# v3.net
KiCad netlist of a schematic drawn in Altium Designer
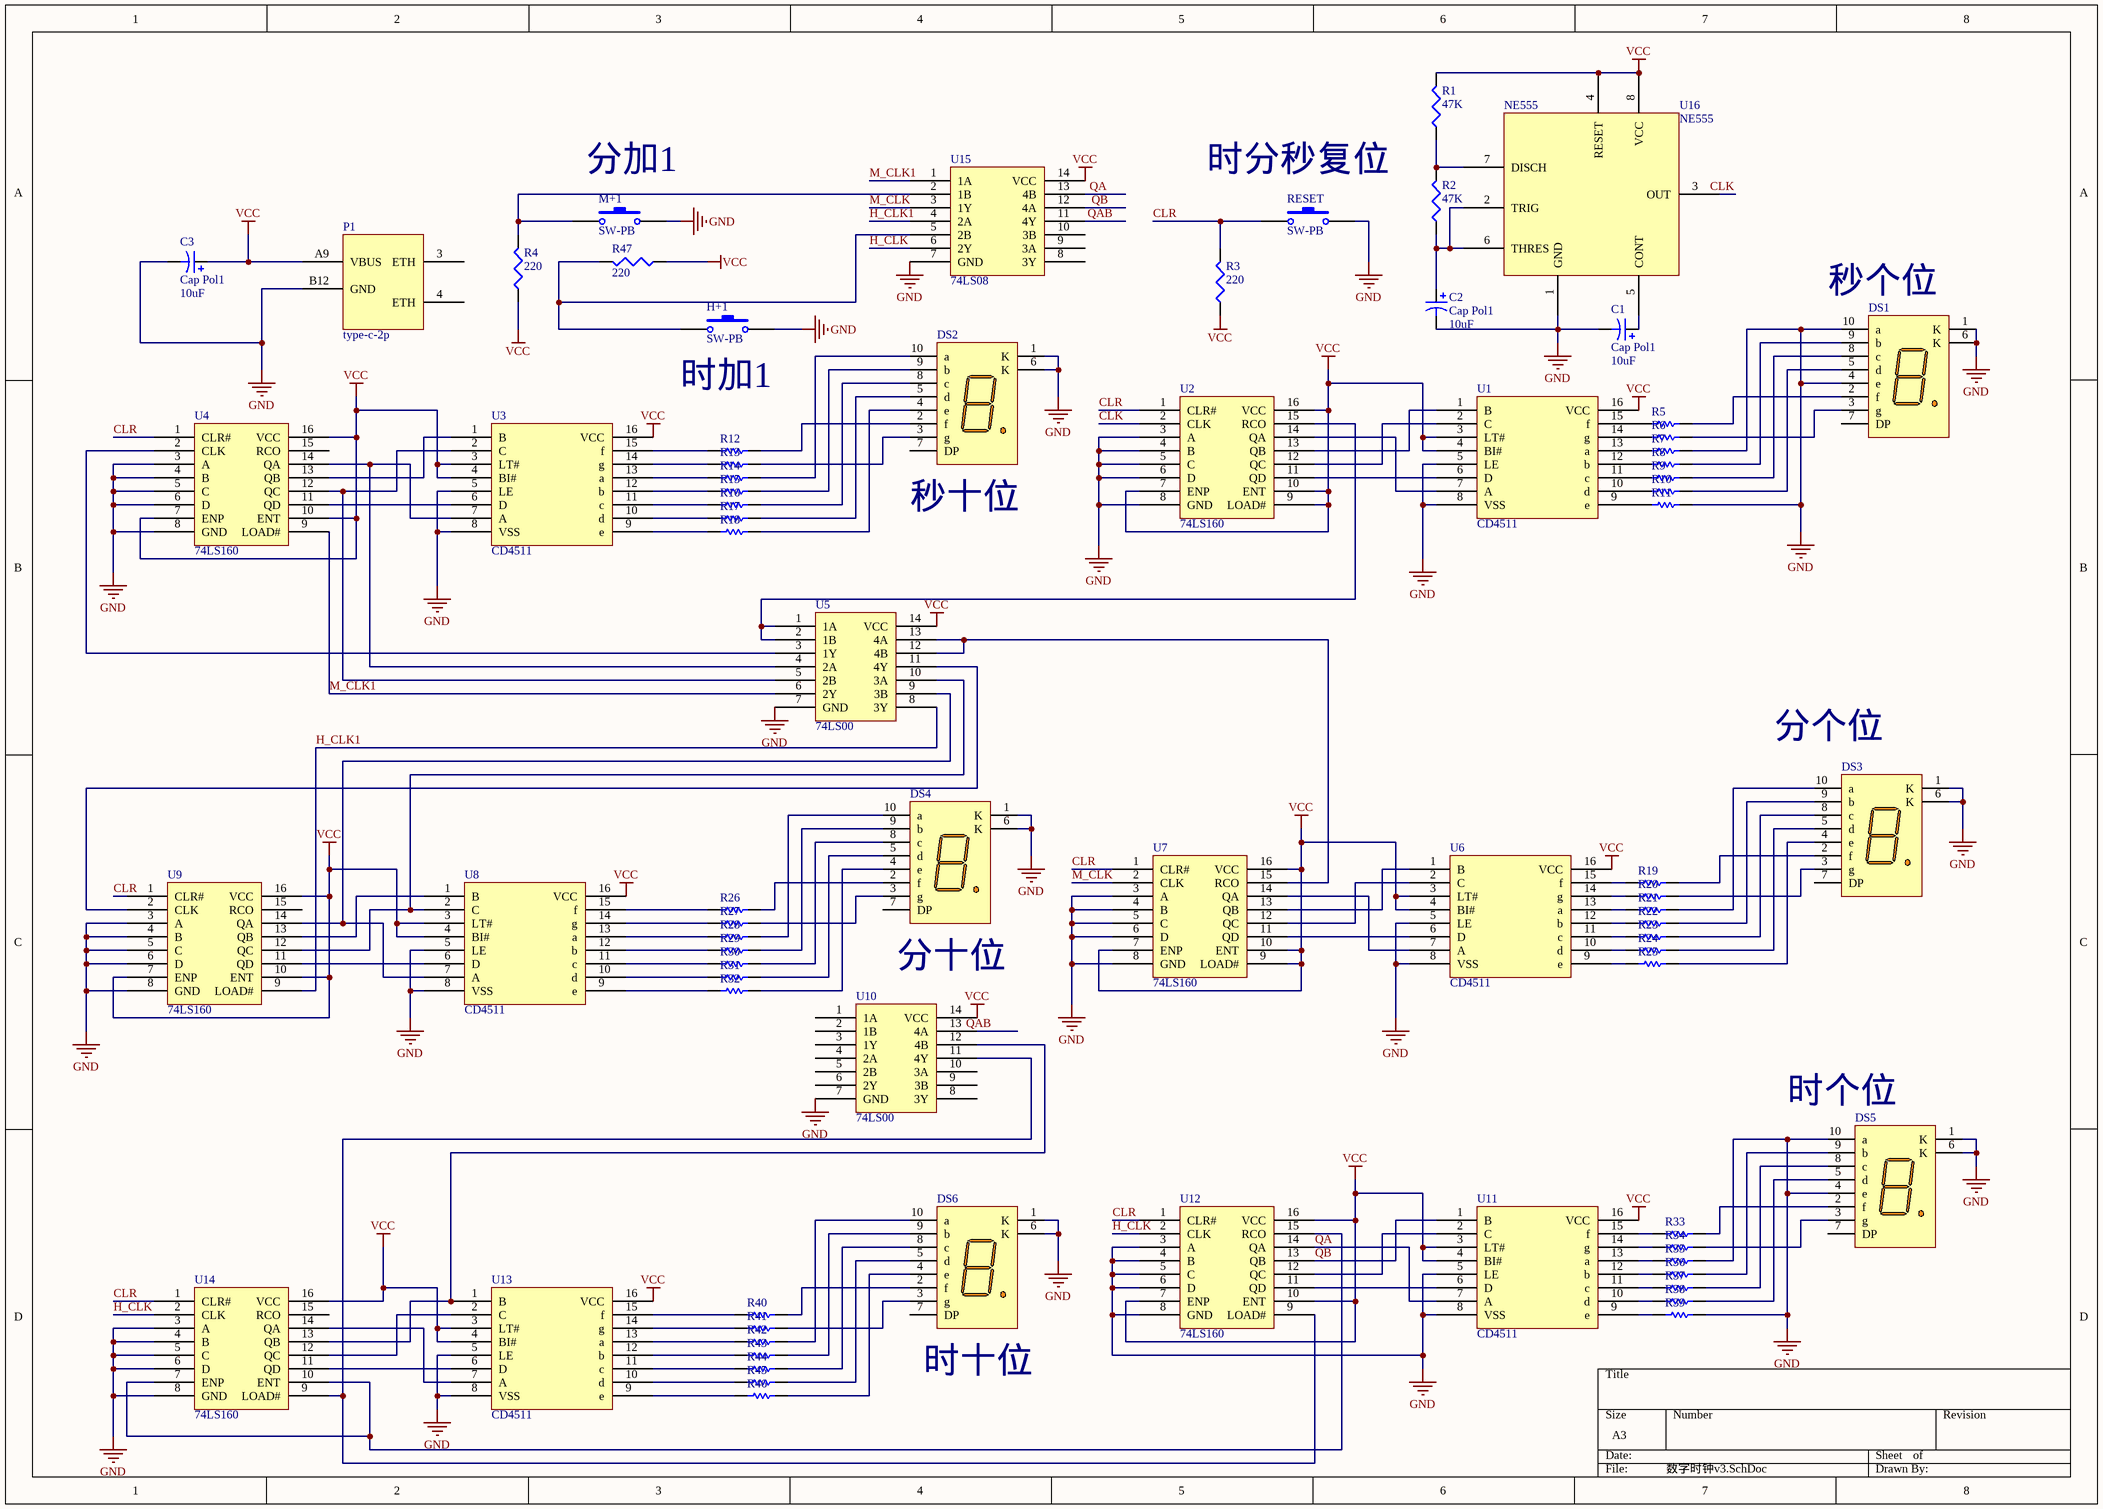
[diagram p0: 数字时钟v3.SchDoc]

(export (version "E")
  (design (tool "Eeschema 10.0.6"))
  (components
    (comp (ref "C1")
      (value "Cap Pol1")
      (footprint "电容")
      (description "Polarized Capacitor (Radial)")
      (fields (field (name "ALTIUM_VALUE") "10uF") (field (name "PUBLISHER") "Altium Limited"))
      (libsource (lib "Miscellaneous Devices") (part "Cap Pol1"))
    )
    (comp (ref "C2")
      (value "Cap Pol1")
      (footprint "电容")
      (description "Polarized Capacitor (Radial)")
      (fields (field (name "ALTIUM_VALUE") "10uF") (field (name "PUBLISHER") "Altium Limited"))
      (libsource (lib "Miscellaneous Devices") (part "Cap Pol1"))
    )
    (comp (ref "C3")
      (value "Cap Pol1")
      (footprint "电容")
      (description "Polarized Capacitor (Radial)")
      (fields (field (name "ALTIUM_VALUE") "10uF") (field (name "PUBLISHER") "Altium Limited"))
      (libsource (lib "Miscellaneous Devices") (part "Cap Pol1"))
    )
    (comp (ref "DS1")
      (value "Dpy Amber-CC")
      (footprint "A")
      (description "7.62 mm Black Surface Orange 7-Segment Display: CC, RH DP")
      (fields (field (name "PUBLISHER") "Altium Limited"))
      (libsource (lib "Miscellaneous Devices") (part "Dpy Amber-CC"))
    )
    (comp (ref "DS2")
      (value "Dpy Amber-CC")
      (footprint "A")
      (description "7.62 mm Black Surface Orange 7-Segment Display: CC, RH DP")
      (fields (field (name "PUBLISHER") "Altium Limited"))
      (libsource (lib "Miscellaneous Devices") (part "Dpy Amber-CC"))
    )
    (comp (ref "DS3")
      (value "Dpy Amber-CC")
      (footprint "A")
      (description "7.62 mm Black Surface Orange 7-Segment Display: CC, RH DP")
      (fields (field (name "PUBLISHER") "Altium Limited"))
      (libsource (lib "Miscellaneous Devices") (part "Dpy Amber-CC"))
    )
    (comp (ref "DS4")
      (value "Dpy Amber-CC")
      (footprint "A")
      (description "7.62 mm Black Surface Orange 7-Segment Display: CC, RH DP")
      (fields (field (name "PUBLISHER") "Altium Limited"))
      (libsource (lib "Miscellaneous Devices") (part "Dpy Amber-CC"))
    )
    (comp (ref "DS5")
      (value "Dpy Amber-CC")
      (footprint "A")
      (description "7.62 mm Black Surface Orange 7-Segment Display: CC, RH DP")
      (fields (field (name "PUBLISHER") "Altium Limited"))
      (libsource (lib "Miscellaneous Devices") (part "Dpy Amber-CC"))
    )
    (comp (ref "DS6")
      (value "Dpy Amber-CC")
      (footprint "A")
      (description "7.62 mm Black Surface Orange 7-Segment Display: CC, RH DP")
      (fields (field (name "PUBLISHER") "Altium Limited"))
      (libsource (lib "Miscellaneous Devices") (part "Dpy Amber-CC"))
    )
    (comp (ref "H+1")
      (value "SW-PB")
      (footprint "按键")
      (description "Switch")
      (fields (field (name "PUBLISHER") "Altium Limited"))
      (libsource (lib "Miscellaneous Devices") (part "SW-PB"))
    )
    (comp (ref "M+1")
      (value "SW-PB")
      (footprint "按键")
      (description "Switch")
      (fields (field (name "PUBLISHER") "Altium Limited"))
      (libsource (lib "Miscellaneous Devices") (part "SW-PB"))
    )
    (comp (ref "P1")
      (value "type-c-2p")
      (footprint "type-c-2p")
      (libsource (lib "数字电路时钟") (part "type-c-2p"))
    )
    (comp (ref "R1")
      (value "47K")
      (footprint "AXIAL-0.3")
      (description "Resistor")
      (fields (field (name "Comment") "Res3") (field (name "PUBLISHER") "Altium Limited"))
      (libsource (lib "Miscellaneous Devices") (part "Res3"))
    )
    (comp (ref "R2")
      (value "47K")
      (footprint "AXIAL-0.3")
      (description "Resistor")
      (fields (field (name "Comment") "Res3") (field (name "PUBLISHER") "Altium Limited"))
      (libsource (lib "Miscellaneous Devices") (part "Res3"))
    )
    (comp (ref "R3")
      (value "220")
      (footprint "AXIAL-0.3")
      (description "Resistor")
      (fields (field (name "Comment") "Res3") (field (name "PUBLISHER") "Altium Limited"))
      (libsource (lib "Miscellaneous Devices") (part "Res3"))
    )
    (comp (ref "R4")
      (value "220")
      (footprint "AXIAL-0.3")
      (description "Resistor")
      (fields (field (name "Comment") "Res3") (field (name "PUBLISHER") "Altium Limited"))
      (libsource (lib "Miscellaneous Devices") (part "Res3"))
    )
    (comp (ref "R5")
      (value "Res1")
      (footprint "AXIAL-0.3")
      (description "Resistor")
      (fields (field (name "PUBLISHER") "Altium Limited"))
      (libsource (lib "Miscellaneous Devices") (part "Res1"))
    )
    (comp (ref "R6")
      (value "Res1")
      (footprint "AXIAL-0.3")
      (description "Resistor")
      (fields (field (name "PUBLISHER") "Altium Limited"))
      (libsource (lib "Miscellaneous Devices") (part "Res1"))
    )
    (comp (ref "R7")
      (value "Res1")
      (footprint "AXIAL-0.3")
      (description "Resistor")
      (fields (field (name "PUBLISHER") "Altium Limited"))
      (libsource (lib "Miscellaneous Devices") (part "Res1"))
    )
    (comp (ref "R8")
      (value "Res1")
      (footprint "AXIAL-0.3")
      (description "Resistor")
      (fields (field (name "PUBLISHER") "Altium Limited"))
      (libsource (lib "Miscellaneous Devices") (part "Res1"))
    )
    (comp (ref "R9")
      (value "Res1")
      (footprint "AXIAL-0.3")
      (description "Resistor")
      (fields (field (name "PUBLISHER") "Altium Limited"))
      (libsource (lib "Miscellaneous Devices") (part "Res1"))
    )
    (comp (ref "R10")
      (value "Res1")
      (footprint "AXIAL-0.3")
      (description "Resistor")
      (fields (field (name "PUBLISHER") "Altium Limited"))
      (libsource (lib "Miscellaneous Devices") (part "Res1"))
    )
    (comp (ref "R11")
      (value "Res1")
      (footprint "AXIAL-0.3")
      (description "Resistor")
      (fields (field (name "PUBLISHER") "Altium Limited"))
      (libsource (lib "Miscellaneous Devices") (part "Res1"))
    )
    (comp (ref "R12")
      (value "Res1")
      (footprint "AXIAL-0.3")
      (description "Resistor")
      (fields (field (name "PUBLISHER") "Altium Limited"))
      (libsource (lib "Miscellaneous Devices") (part "Res1"))
    )
    (comp (ref "R13")
      (value "Res1")
      (footprint "AXIAL-0.3")
      (description "Resistor")
      (fields (field (name "PUBLISHER") "Altium Limited"))
      (libsource (lib "Miscellaneous Devices") (part "Res1"))
    )
    (comp (ref "R14")
      (value "Res1")
      (footprint "AXIAL-0.3")
      (description "Resistor")
      (fields (field (name "PUBLISHER") "Altium Limited"))
      (libsource (lib "Miscellaneous Devices") (part "Res1"))
    )
    (comp (ref "R15")
      (value "Res1")
      (footprint "AXIAL-0.3")
      (description "Resistor")
      (fields (field (name "PUBLISHER") "Altium Limited"))
      (libsource (lib "Miscellaneous Devices") (part "Res1"))
    )
    (comp (ref "R16")
      (value "Res1")
      (footprint "AXIAL-0.3")
      (description "Resistor")
      (fields (field (name "PUBLISHER") "Altium Limited"))
      (libsource (lib "Miscellaneous Devices") (part "Res1"))
    )
    (comp (ref "R17")
      (value "Res1")
      (footprint "AXIAL-0.3")
      (description "Resistor")
      (fields (field (name "PUBLISHER") "Altium Limited"))
      (libsource (lib "Miscellaneous Devices") (part "Res1"))
    )
    (comp (ref "R18")
      (value "Res1")
      (footprint "AXIAL-0.3")
      (description "Resistor")
      (fields (field (name "PUBLISHER") "Altium Limited"))
      (libsource (lib "Miscellaneous Devices") (part "Res1"))
    )
    (comp (ref "R19")
      (value "Res1")
      (footprint "AXIAL-0.3")
      (description "Resistor")
      (fields (field (name "PUBLISHER") "Altium Limited"))
      (libsource (lib "Miscellaneous Devices") (part "Res1"))
    )
    (comp (ref "R20")
      (value "Res1")
      (footprint "AXIAL-0.3")
      (description "Resistor")
      (fields (field (name "PUBLISHER") "Altium Limited"))
      (libsource (lib "Miscellaneous Devices") (part "Res1"))
    )
    (comp (ref "R21")
      (value "Res1")
      (footprint "AXIAL-0.3")
      (description "Resistor")
      (fields (field (name "PUBLISHER") "Altium Limited"))
      (libsource (lib "Miscellaneous Devices") (part "Res1"))
    )
    (comp (ref "R22")
      (value "Res1")
      (footprint "AXIAL-0.3")
      (description "Resistor")
      (fields (field (name "PUBLISHER") "Altium Limited"))
      (libsource (lib "Miscellaneous Devices") (part "Res1"))
    )
    (comp (ref "R23")
      (value "Res1")
      (footprint "AXIAL-0.3")
      (description "Resistor")
      (fields (field (name "PUBLISHER") "Altium Limited"))
      (libsource (lib "Miscellaneous Devices") (part "Res1"))
    )
    (comp (ref "R24")
      (value "Res1")
      (footprint "AXIAL-0.3")
      (description "Resistor")
      (fields (field (name "PUBLISHER") "Altium Limited"))
      (libsource (lib "Miscellaneous Devices") (part "Res1"))
    )
    (comp (ref "R25")
      (value "Res1")
      (footprint "AXIAL-0.3")
      (description "Resistor")
      (fields (field (name "PUBLISHER") "Altium Limited"))
      (libsource (lib "Miscellaneous Devices") (part "Res1"))
    )
    (comp (ref "R26")
      (value "Res1")
      (footprint "AXIAL-0.3")
      (description "Resistor")
      (fields (field (name "PUBLISHER") "Altium Limited"))
      (libsource (lib "Miscellaneous Devices") (part "Res1"))
    )
    (comp (ref "R27")
      (value "Res1")
      (footprint "AXIAL-0.3")
      (description "Resistor")
      (fields (field (name "PUBLISHER") "Altium Limited"))
      (libsource (lib "Miscellaneous Devices") (part "Res1"))
    )
    (comp (ref "R28")
      (value "Res1")
      (footprint "AXIAL-0.3")
      (description "Resistor")
      (fields (field (name "PUBLISHER") "Altium Limited"))
      (libsource (lib "Miscellaneous Devices") (part "Res1"))
    )
    (comp (ref "R29")
      (value "Res1")
      (footprint "AXIAL-0.3")
      (description "Resistor")
      (fields (field (name "PUBLISHER") "Altium Limited"))
      (libsource (lib "Miscellaneous Devices") (part "Res1"))
    )
    (comp (ref "R30")
      (value "Res1")
      (footprint "AXIAL-0.3")
      (description "Resistor")
      (fields (field (name "PUBLISHER") "Altium Limited"))
      (libsource (lib "Miscellaneous Devices") (part "Res1"))
    )
    (comp (ref "R31")
      (value "Res1")
      (footprint "AXIAL-0.3")
      (description "Resistor")
      (fields (field (name "PUBLISHER") "Altium Limited"))
      (libsource (lib "Miscellaneous Devices") (part "Res1"))
    )
    (comp (ref "R32")
      (value "Res1")
      (footprint "AXIAL-0.3")
      (description "Resistor")
      (fields (field (name "PUBLISHER") "Altium Limited"))
      (libsource (lib "Miscellaneous Devices") (part "Res1"))
    )
    (comp (ref "R33")
      (value "Res1")
      (footprint "AXIAL-0.3")
      (description "Resistor")
      (fields (field (name "PUBLISHER") "Altium Limited"))
      (libsource (lib "Miscellaneous Devices") (part "Res1"))
    )
    (comp (ref "R34")
      (value "Res1")
      (footprint "AXIAL-0.3")
      (description "Resistor")
      (fields (field (name "PUBLISHER") "Altium Limited"))
      (libsource (lib "Miscellaneous Devices") (part "Res1"))
    )
    (comp (ref "R35")
      (value "Res1")
      (footprint "AXIAL-0.3")
      (description "Resistor")
      (fields (field (name "PUBLISHER") "Altium Limited"))
      (libsource (lib "Miscellaneous Devices") (part "Res1"))
    )
    (comp (ref "R36")
      (value "Res1")
      (footprint "AXIAL-0.3")
      (description "Resistor")
      (fields (field (name "PUBLISHER") "Altium Limited"))
      (libsource (lib "Miscellaneous Devices") (part "Res1"))
    )
    (comp (ref "R37")
      (value "Res1")
      (footprint "AXIAL-0.3")
      (description "Resistor")
      (fields (field (name "PUBLISHER") "Altium Limited"))
      (libsource (lib "Miscellaneous Devices") (part "Res1"))
    )
    (comp (ref "R38")
      (value "Res1")
      (footprint "AXIAL-0.3")
      (description "Resistor")
      (fields (field (name "PUBLISHER") "Altium Limited"))
      (libsource (lib "Miscellaneous Devices") (part "Res1"))
    )
    (comp (ref "R39")
      (value "Res1")
      (footprint "AXIAL-0.3")
      (description "Resistor")
      (fields (field (name "PUBLISHER") "Altium Limited"))
      (libsource (lib "Miscellaneous Devices") (part "Res1"))
    )
    (comp (ref "R40")
      (value "Res1")
      (footprint "AXIAL-0.3")
      (description "Resistor")
      (fields (field (name "PUBLISHER") "Altium Limited"))
      (libsource (lib "Miscellaneous Devices") (part "Res1"))
    )
    (comp (ref "R41")
      (value "Res1")
      (footprint "AXIAL-0.3")
      (description "Resistor")
      (fields (field (name "PUBLISHER") "Altium Limited"))
      (libsource (lib "Miscellaneous Devices") (part "Res1"))
    )
    (comp (ref "R42")
      (value "Res1")
      (footprint "AXIAL-0.3")
      (description "Resistor")
      (fields (field (name "PUBLISHER") "Altium Limited"))
      (libsource (lib "Miscellaneous Devices") (part "Res1"))
    )
    (comp (ref "R43")
      (value "Res1")
      (footprint "AXIAL-0.3")
      (description "Resistor")
      (fields (field (name "PUBLISHER") "Altium Limited"))
      (libsource (lib "Miscellaneous Devices") (part "Res1"))
    )
    (comp (ref "R44")
      (value "Res1")
      (footprint "AXIAL-0.3")
      (description "Resistor")
      (fields (field (name "PUBLISHER") "Altium Limited"))
      (libsource (lib "Miscellaneous Devices") (part "Res1"))
    )
    (comp (ref "R45")
      (value "Res1")
      (footprint "AXIAL-0.3")
      (description "Resistor")
      (fields (field (name "PUBLISHER") "Altium Limited"))
      (libsource (lib "Miscellaneous Devices") (part "Res1"))
    )
    (comp (ref "R46")
      (value "Res1")
      (footprint "AXIAL-0.3")
      (description "Resistor")
      (fields (field (name "PUBLISHER") "Altium Limited"))
      (libsource (lib "Miscellaneous Devices") (part "Res1"))
    )
    (comp (ref "R47")
      (value "220")
      (footprint "AXIAL-0.3")
      (description "Resistor")
      (fields (field (name "Comment") "Res3") (field (name "PUBLISHER") "Altium Limited"))
      (libsource (lib "Miscellaneous Devices") (part "Res3"))
    )
    (comp (ref "RESET")
      (value "SW-PB")
      (footprint "按键")
      (description "Switch")
      (fields (field (name "PUBLISHER") "Altium Limited"))
      (libsource (lib "Miscellaneous Devices") (part "SW-PB"))
    )
    (comp (ref "U1") (value "CD4511") (footprint "CD4511BM/TR") (libsource (lib "数字电路时钟") (part "CD4511")))
    (comp (ref "U2") (value "74LS160") (footprint "DIP-16") (libsource (lib "数字电路时钟") (part "74LS160")))
    (comp (ref "U3") (value "CD4511") (footprint "CD4511BM/TR") (libsource (lib "数字电路时钟") (part "CD4511")))
    (comp (ref "U4") (value "74LS160") (footprint "DIP-16") (libsource (lib "数字电路时钟") (part "74LS160")))
    (comp (ref "U5") (value "74LS00") (footprint "DIP-14") (libsource (lib "数字电路时钟") (part "74LS00")))
    (comp (ref "U6") (value "CD4511") (footprint "CD4511BM/TR") (libsource (lib "数字电路时钟") (part "CD4511")))
    (comp (ref "U7") (value "74LS160") (footprint "DIP-16") (libsource (lib "数字电路时钟") (part "74LS160")))
    (comp (ref "U8") (value "CD4511") (footprint "CD4511BM/TR") (libsource (lib "数字电路时钟") (part "CD4511")))
    (comp (ref "U9") (value "74LS160") (footprint "DIP-16") (libsource (lib "数字电路时钟") (part "74LS160")))
    (comp (ref "U10") (value "74LS00") (footprint "DIP-14") (libsource (lib "数字电路时钟") (part "74LS00")))
    (comp (ref "U11") (value "CD4511") (footprint "CD4511BM/TR") (libsource (lib "数字电路时钟") (part "CD4511")))
    (comp (ref "U12") (value "74LS160") (footprint "DIP-16") (libsource (lib "数字电路时钟") (part "74LS160")))
    (comp (ref "U13") (value "CD4511") (footprint "CD4511BM/TR") (libsource (lib "数字电路时钟") (part "CD4511")))
    (comp (ref "U14") (value "74LS160") (footprint "DIP-16") (libsource (lib "数字电路时钟") (part "74LS160")))
    (comp (ref "U15") (value "74LS08") (footprint "DIP-14") (libsource (lib "数字电路时钟") (part "74LS08")))
    (comp (ref "U16") (value "NE555") (footprint "DIP-8") (libsource (lib "数字电路时钟") (part "NE555")))
  )
  (nets
    (net (code "1") (name "/CLK") (class "Default")
      (node (ref "U16") (pin "3") (pinfunction "OUT_3") (pintype "passive"))
      (node (ref "U2") (pin "2") (pinfunction "CLK_2") (pintype "passive"))
    )
    (net (code "2") (name "/CLR") (class "Default")
      (node (ref "R3") (pin "2") (pinfunction "2_2") (pintype "passive"))
      (node (ref "RESET") (pin "1") (pinfunction "1_1") (pintype "passive"))
      (node (ref "U12") (pin "1") (pinfunction "CLR#_1") (pintype "passive"))
      (node (ref "U14") (pin "1") (pinfunction "CLR#_1") (pintype "passive"))
      (node (ref "U2") (pin "1") (pinfunction "CLR#_1") (pintype "passive"))
      (node (ref "U4") (pin "1") (pinfunction "CLR#_1") (pintype "passive"))
      (node (ref "U7") (pin "1") (pinfunction "CLR#_1") (pintype "passive"))
      (node (ref "U9") (pin "1") (pinfunction "CLR#_1") (pintype "passive"))
    )
    (net (code "3") (name "/H_CLK") (class "Default")
      (node (ref "U12") (pin "2") (pinfunction "CLK_2") (pintype "passive"))
      (node (ref "U14") (pin "2") (pinfunction "CLK_2") (pintype "passive"))
      (node (ref "U15") (pin "6") (pinfunction "2Y_6") (pintype "passive"))
    )
    (net (code "4") (name "/H_CLK1") (class "Default")
      (node (ref "U15") (pin "4") (pinfunction "2A_4") (pintype "passive"))
      (node (ref "U5") (pin "8") (pinfunction "3Y_8") (pintype "passive"))
      (node (ref "U9") (pin "9") (pinfunction "LOAD#_9") (pintype "passive"))
    )
    (net (code "5") (name "/M_CLK") (class "Default")
      (node (ref "U15") (pin "3") (pinfunction "1Y_3") (pintype "passive"))
      (node (ref "U7") (pin "2") (pinfunction "CLK_2") (pintype "passive"))
    )
    (net (code "6") (name "/M_CLK1") (class "Default")
      (node (ref "U15") (pin "1") (pinfunction "1A_1") (pintype "passive"))
      (node (ref "U4") (pin "9") (pinfunction "LOAD#_9") (pintype "passive"))
      (node (ref "U5") (pin "6") (pinfunction "2Y_6") (pintype "passive"))
    )
    (net (code "7") (name "/QA") (class "Default")
      (node (ref "U11") (pin "7") (pinfunction "A_7") (pintype "passive"))
      (node (ref "U12") (pin "14") (pinfunction "QA_14") (pintype "passive"))
      (node (ref "U15") (pin "13") (pinfunction "4B_13") (pintype "passive"))
    )
    (net (code "8") (name "/QAB") (class "Default")
      (node (ref "U10") (pin "13") (pinfunction "4A_13") (pintype "passive"))
      (node (ref "U15") (pin "11") (pinfunction "4Y_11") (pintype "passive"))
    )
    (net (code "9") (name "/QB") (class "Default")
      (node (ref "U11") (pin "1") (pinfunction "B_1") (pintype "passive"))
      (node (ref "U12") (pin "13") (pinfunction "QB_13") (pintype "passive"))
      (node (ref "U15") (pin "12") (pinfunction "4A_12") (pintype "passive"))
    )
    (net (code "10") (name "GND") (class "Default")
      (node (ref "C1") (pin "2") (pinfunction "2_2") (pintype "passive"))
      (node (ref "C2") (pin "2") (pinfunction "2_2") (pintype "passive"))
      (node (ref "C3") (pin "2") (pinfunction "2_2") (pintype "passive"))
      (node (ref "DS1") (pin "1") (pinfunction "K_1") (pintype "passive"))
      (node (ref "DS1") (pin "10") (pinfunction "a_10") (pintype "passive"))
      (node (ref "DS1") (pin "4") (pinfunction "e_4") (pintype "passive"))
      (node (ref "DS1") (pin "6") (pinfunction "K_6") (pintype "passive"))
      (node (ref "DS2") (pin "1") (pinfunction "K_1") (pintype "passive"))
      (node (ref "DS2") (pin "6") (pinfunction "K_6") (pintype "passive"))
      (node (ref "DS3") (pin "1") (pinfunction "K_1") (pintype "passive"))
      (node (ref "DS3") (pin "6") (pinfunction "K_6") (pintype "passive"))
      (node (ref "DS4") (pin "1") (pinfunction "K_1") (pintype "passive"))
      (node (ref "DS4") (pin "6") (pinfunction "K_6") (pintype "passive"))
      (node (ref "DS5") (pin "1") (pinfunction "K_1") (pintype "passive"))
      (node (ref "DS5") (pin "10") (pinfunction "a_10") (pintype "passive"))
      (node (ref "DS5") (pin "4") (pinfunction "e_4") (pintype "passive"))
      (node (ref "DS5") (pin "6") (pinfunction "K_6") (pintype "passive"))
      (node (ref "DS6") (pin "1") (pinfunction "K_1") (pintype "passive"))
      (node (ref "DS6") (pin "6") (pinfunction "K_6") (pintype "passive"))
      (node (ref "H+1") (pin "2") (pinfunction "2_2") (pintype "passive"))
      (node (ref "M+1") (pin "2") (pinfunction "2_2") (pintype "passive"))
      (node (ref "P1") (pin "B12") (pinfunction "GND_B12") (pintype "passive"))
      (node (ref "R11") (pin "2") (pinfunction "2_2") (pintype "passive"))
      (node (ref "R35") (pin "2") (pinfunction "2_2") (pintype "passive"))
      (node (ref "R39") (pin "2") (pinfunction "2_2") (pintype "passive"))
      (node (ref "R7") (pin "2") (pinfunction "2_2") (pintype "passive"))
      (node (ref "RESET") (pin "2") (pinfunction "2_2") (pintype "passive"))
      (node (ref "U1") (pin "5") (pinfunction "LE_5") (pintype "passive"))
      (node (ref "U1") (pin "8") (pinfunction "VSS_8") (pintype "passive"))
      (node (ref "U10") (pin "7") (pinfunction "GND_7") (pintype "passive"))
      (node (ref "U11") (pin "5") (pinfunction "LE_5") (pintype "passive"))
      (node (ref "U11") (pin "8") (pinfunction "VSS_8") (pintype "passive"))
      (node (ref "U12") (pin "3") (pinfunction "A_3") (pintype "passive"))
      (node (ref "U12") (pin "4") (pinfunction "B_4") (pintype "passive"))
      (node (ref "U12") (pin "5") (pinfunction "C_5") (pintype "passive"))
      (node (ref "U12") (pin "6") (pinfunction "D_6") (pintype "passive"))
      (node (ref "U12") (pin "8") (pinfunction "GND_8") (pintype "passive"))
      (node (ref "U13") (pin "5") (pinfunction "LE_5") (pintype "passive"))
      (node (ref "U13") (pin "8") (pinfunction "VSS_8") (pintype "passive"))
      (node (ref "U14") (pin "3") (pinfunction "A_3") (pintype "passive"))
      (node (ref "U14") (pin "4") (pinfunction "B_4") (pintype "passive"))
      (node (ref "U14") (pin "5") (pinfunction "C_5") (pintype "passive"))
      (node (ref "U14") (pin "6") (pinfunction "D_6") (pintype "passive"))
      (node (ref "U14") (pin "8") (pinfunction "GND_8") (pintype "passive"))
      (node (ref "U15") (pin "7") (pinfunction "GND_7") (pintype "passive"))
      (node (ref "U16") (pin "1") (pinfunction "GND_1") (pintype "passive"))
      (node (ref "U2") (pin "3") (pinfunction "A_3") (pintype "passive"))
      (node (ref "U2") (pin "4") (pinfunction "B_4") (pintype "passive"))
      (node (ref "U2") (pin "5") (pinfunction "C_5") (pintype "passive"))
      (node (ref "U2") (pin "6") (pinfunction "D_6") (pintype "passive"))
      (node (ref "U2") (pin "8") (pinfunction "GND_8") (pintype "passive"))
      (node (ref "U3") (pin "5") (pinfunction "LE_5") (pintype "passive"))
      (node (ref "U3") (pin "8") (pinfunction "VSS_8") (pintype "passive"))
      (node (ref "U4") (pin "3") (pinfunction "A_3") (pintype "passive"))
      (node (ref "U4") (pin "4") (pinfunction "B_4") (pintype "passive"))
      (node (ref "U4") (pin "5") (pinfunction "C_5") (pintype "passive"))
      (node (ref "U4") (pin "6") (pinfunction "D_6") (pintype "passive"))
      (node (ref "U4") (pin "8") (pinfunction "GND_8") (pintype "passive"))
      (node (ref "U5") (pin "7") (pinfunction "GND_7") (pintype "passive"))
      (node (ref "U6") (pin "5") (pinfunction "LE_5") (pintype "passive"))
      (node (ref "U6") (pin "8") (pinfunction "VSS_8") (pintype "passive"))
      (node (ref "U7") (pin "3") (pinfunction "A_3") (pintype "passive"))
      (node (ref "U7") (pin "4") (pinfunction "B_4") (pintype "passive"))
      (node (ref "U7") (pin "5") (pinfunction "C_5") (pintype "passive"))
      (node (ref "U7") (pin "6") (pinfunction "D_6") (pintype "passive"))
      (node (ref "U7") (pin "8") (pinfunction "GND_8") (pintype "passive"))
      (node (ref "U8") (pin "5") (pinfunction "LE_5") (pintype "passive"))
      (node (ref "U8") (pin "8") (pinfunction "VSS_8") (pintype "passive"))
      (node (ref "U9") (pin "3") (pinfunction "A_3") (pintype "passive"))
      (node (ref "U9") (pin "4") (pinfunction "B_4") (pintype "passive"))
      (node (ref "U9") (pin "5") (pinfunction "C_5") (pintype "passive"))
      (node (ref "U9") (pin "6") (pinfunction "D_6") (pintype "passive"))
      (node (ref "U9") (pin "8") (pinfunction "GND_8") (pintype "passive"))
    )
    (net (code "11") (name "Net-(DS1-b)") (class "Default")
      (node (ref "DS1") (pin "9") (pinfunction "b_9") (pintype "passive"))
      (node (ref "R8") (pin "2") (pinfunction "2_2") (pintype "passive"))
    )
    (net (code "12") (name "Net-(DS1-c)") (class "Default")
      (node (ref "DS1") (pin "8") (pinfunction "c_8") (pintype "passive"))
      (node (ref "R9") (pin "2") (pinfunction "2_2") (pintype "passive"))
    )
    (net (code "13") (name "Net-(DS1-d)") (class "Default")
      (node (ref "DS1") (pin "5") (pinfunction "d_5") (pintype "passive"))
      (node (ref "R10") (pin "2") (pinfunction "2_2") (pintype "passive"))
    )
    (net (code "14") (name "Net-(DS1-f)") (class "Default")
      (node (ref "DS1") (pin "2") (pinfunction "f_2") (pintype "passive"))
      (node (ref "R5") (pin "2") (pinfunction "2_2") (pintype "passive"))
    )
    (net (code "15") (name "Net-(DS1-g)") (class "Default")
      (node (ref "DS1") (pin "3") (pinfunction "g_3") (pintype "passive"))
      (node (ref "R6") (pin "2") (pinfunction "2_2") (pintype "passive"))
    )
    (net (code "16") (name "Net-(DS2-a)") (class "Default")
      (node (ref "DS2") (pin "10") (pinfunction "a_10") (pintype "passive"))
      (node (ref "R14") (pin "2") (pinfunction "2_2") (pintype "passive"))
    )
    (net (code "17") (name "Net-(DS2-b)") (class "Default")
      (node (ref "DS2") (pin "9") (pinfunction "b_9") (pintype "passive"))
      (node (ref "R15") (pin "2") (pinfunction "2_2") (pintype "passive"))
    )
    (net (code "18") (name "Net-(DS2-c)") (class "Default")
      (node (ref "DS2") (pin "8") (pinfunction "c_8") (pintype "passive"))
      (node (ref "R16") (pin "2") (pinfunction "2_2") (pintype "passive"))
    )
    (net (code "19") (name "Net-(DS2-d)") (class "Default")
      (node (ref "DS2") (pin "5") (pinfunction "d_5") (pintype "passive"))
      (node (ref "R17") (pin "2") (pinfunction "2_2") (pintype "passive"))
    )
    (net (code "20") (name "Net-(DS2-e)") (class "Default")
      (node (ref "DS2") (pin "4") (pinfunction "e_4") (pintype "passive"))
      (node (ref "R18") (pin "2") (pinfunction "2_2") (pintype "passive"))
    )
    (net (code "21") (name "Net-(DS2-f)") (class "Default")
      (node (ref "DS2") (pin "2") (pinfunction "f_2") (pintype "passive"))
      (node (ref "R12") (pin "2") (pinfunction "2_2") (pintype "passive"))
    )
    (net (code "22") (name "Net-(DS2-g)") (class "Default")
      (node (ref "DS2") (pin "3") (pinfunction "g_3") (pintype "passive"))
      (node (ref "R13") (pin "2") (pinfunction "2_2") (pintype "passive"))
    )
    (net (code "23") (name "Net-(DS3-a)") (class "Default")
      (node (ref "DS3") (pin "10") (pinfunction "a_10") (pintype "passive"))
      (node (ref "R21") (pin "2") (pinfunction "2_2") (pintype "passive"))
    )
    (net (code "24") (name "Net-(DS3-b)") (class "Default")
      (node (ref "DS3") (pin "9") (pinfunction "b_9") (pintype "passive"))
      (node (ref "R22") (pin "2") (pinfunction "2_2") (pintype "passive"))
    )
    (net (code "25") (name "Net-(DS3-c)") (class "Default")
      (node (ref "DS3") (pin "8") (pinfunction "c_8") (pintype "passive"))
      (node (ref "R23") (pin "2") (pinfunction "2_2") (pintype "passive"))
    )
    (net (code "26") (name "Net-(DS3-d)") (class "Default")
      (node (ref "DS3") (pin "5") (pinfunction "d_5") (pintype "passive"))
      (node (ref "R24") (pin "2") (pinfunction "2_2") (pintype "passive"))
    )
    (net (code "27") (name "Net-(DS3-e)") (class "Default")
      (node (ref "DS3") (pin "4") (pinfunction "e_4") (pintype "passive"))
      (node (ref "R25") (pin "2") (pinfunction "2_2") (pintype "passive"))
    )
    (net (code "28") (name "Net-(DS3-f)") (class "Default")
      (node (ref "DS3") (pin "2") (pinfunction "f_2") (pintype "passive"))
      (node (ref "R19") (pin "2") (pinfunction "2_2") (pintype "passive"))
    )
    (net (code "29") (name "Net-(DS3-g)") (class "Default")
      (node (ref "DS3") (pin "3") (pinfunction "g_3") (pintype "passive"))
      (node (ref "R20") (pin "2") (pinfunction "2_2") (pintype "passive"))
    )
    (net (code "30") (name "Net-(DS4-a)") (class "Default")
      (node (ref "DS4") (pin "10") (pinfunction "a_10") (pintype "passive"))
      (node (ref "R28") (pin "2") (pinfunction "2_2") (pintype "passive"))
    )
    (net (code "31") (name "Net-(DS4-b)") (class "Default")
      (node (ref "DS4") (pin "9") (pinfunction "b_9") (pintype "passive"))
      (node (ref "R29") (pin "2") (pinfunction "2_2") (pintype "passive"))
    )
    (net (code "32") (name "Net-(DS4-c)") (class "Default")
      (node (ref "DS4") (pin "8") (pinfunction "c_8") (pintype "passive"))
      (node (ref "R30") (pin "2") (pinfunction "2_2") (pintype "passive"))
    )
    (net (code "33") (name "Net-(DS4-d)") (class "Default")
      (node (ref "DS4") (pin "5") (pinfunction "d_5") (pintype "passive"))
      (node (ref "R31") (pin "2") (pinfunction "2_2") (pintype "passive"))
    )
    (net (code "34") (name "Net-(DS4-e)") (class "Default")
      (node (ref "DS4") (pin "4") (pinfunction "e_4") (pintype "passive"))
      (node (ref "R32") (pin "2") (pinfunction "2_2") (pintype "passive"))
    )
    (net (code "35") (name "Net-(DS4-f)") (class "Default")
      (node (ref "DS4") (pin "2") (pinfunction "f_2") (pintype "passive"))
      (node (ref "R26") (pin "2") (pinfunction "2_2") (pintype "passive"))
    )
    (net (code "36") (name "Net-(DS4-g)") (class "Default")
      (node (ref "DS4") (pin "3") (pinfunction "g_3") (pintype "passive"))
      (node (ref "R27") (pin "2") (pinfunction "2_2") (pintype "passive"))
    )
    (net (code "37") (name "Net-(DS5-b)") (class "Default")
      (node (ref "DS5") (pin "9") (pinfunction "b_9") (pintype "passive"))
      (node (ref "R36") (pin "2") (pinfunction "2_2") (pintype "passive"))
    )
    (net (code "38") (name "Net-(DS5-c)") (class "Default")
      (node (ref "DS5") (pin "8") (pinfunction "c_8") (pintype "passive"))
      (node (ref "R37") (pin "2") (pinfunction "2_2") (pintype "passive"))
    )
    (net (code "39") (name "Net-(DS5-d)") (class "Default")
      (node (ref "DS5") (pin "5") (pinfunction "d_5") (pintype "passive"))
      (node (ref "R38") (pin "2") (pinfunction "2_2") (pintype "passive"))
    )
    (net (code "40") (name "Net-(DS5-f)") (class "Default")
      (node (ref "DS5") (pin "2") (pinfunction "f_2") (pintype "passive"))
      (node (ref "R33") (pin "2") (pinfunction "2_2") (pintype "passive"))
    )
    (net (code "41") (name "Net-(DS5-g)") (class "Default")
      (node (ref "DS5") (pin "3") (pinfunction "g_3") (pintype "passive"))
      (node (ref "R34") (pin "2") (pinfunction "2_2") (pintype "passive"))
    )
    (net (code "42") (name "Net-(DS6-a)") (class "Default")
      (node (ref "DS6") (pin "10") (pinfunction "a_10") (pintype "passive"))
      (node (ref "R42") (pin "2") (pinfunction "2_2") (pintype "passive"))
    )
    (net (code "43") (name "Net-(DS6-b)") (class "Default")
      (node (ref "DS6") (pin "9") (pinfunction "b_9") (pintype "passive"))
      (node (ref "R43") (pin "2") (pinfunction "2_2") (pintype "passive"))
    )
    (net (code "44") (name "Net-(DS6-c)") (class "Default")
      (node (ref "DS6") (pin "8") (pinfunction "c_8") (pintype "passive"))
      (node (ref "R44") (pin "2") (pinfunction "2_2") (pintype "passive"))
    )
    (net (code "45") (name "Net-(DS6-d)") (class "Default")
      (node (ref "DS6") (pin "5") (pinfunction "d_5") (pintype "passive"))
      (node (ref "R45") (pin "2") (pinfunction "2_2") (pintype "passive"))
    )
    (net (code "46") (name "Net-(DS6-e)") (class "Default")
      (node (ref "DS6") (pin "4") (pinfunction "e_4") (pintype "passive"))
      (node (ref "R46") (pin "2") (pinfunction "2_2") (pintype "passive"))
    )
    (net (code "47") (name "Net-(DS6-f)") (class "Default")
      (node (ref "DS6") (pin "2") (pinfunction "f_2") (pintype "passive"))
      (node (ref "R40") (pin "2") (pinfunction "2_2") (pintype "passive"))
    )
    (net (code "48") (name "Net-(DS6-g)") (class "Default")
      (node (ref "DS6") (pin "3") (pinfunction "g_3") (pintype "passive"))
      (node (ref "R41") (pin "2") (pinfunction "2_2") (pintype "passive"))
    )
    (net (code "49") (name "Net-(U1-A)") (class "Default")
      (node (ref "U1") (pin "7") (pinfunction "A_7") (pintype "passive"))
      (node (ref "U2") (pin "14") (pinfunction "QA_14") (pintype "passive"))
    )
    (net (code "50") (name "Net-(U1-B)") (class "Default")
      (node (ref "U1") (pin "1") (pinfunction "B_1") (pintype "passive"))
      (node (ref "U2") (pin "13") (pinfunction "QB_13") (pintype "passive"))
    )
    (net (code "51") (name "Net-(U1-C)") (class "Default")
      (node (ref "U1") (pin "2") (pinfunction "C_2") (pintype "passive"))
      (node (ref "U2") (pin "12") (pinfunction "QC_12") (pintype "passive"))
    )
    (net (code "52") (name "Net-(U1-D)") (class "Default")
      (node (ref "U1") (pin "6") (pinfunction "D_6") (pintype "passive"))
      (node (ref "U2") (pin "11") (pinfunction "QD_11") (pintype "passive"))
    )
    (net (code "53") (name "Net-(U1-a)") (class "Default")
      (node (ref "R7") (pin "1") (pinfunction "1_1") (pintype "passive"))
      (node (ref "U1") (pin "13") (pinfunction "a_13") (pintype "passive"))
    )
    (net (code "54") (name "Net-(U1-b)") (class "Default")
      (node (ref "R8") (pin "1") (pinfunction "1_1") (pintype "passive"))
      (node (ref "U1") (pin "12") (pinfunction "b_12") (pintype "passive"))
    )
    (net (code "55") (name "Net-(U1-c)") (class "Default")
      (node (ref "R9") (pin "1") (pinfunction "1_1") (pintype "passive"))
      (node (ref "U1") (pin "11") (pinfunction "c_11") (pintype "passive"))
    )
    (net (code "56") (name "Net-(U1-d)") (class "Default")
      (node (ref "R10") (pin "1") (pinfunction "1_1") (pintype "passive"))
      (node (ref "U1") (pin "10") (pinfunction "d_10") (pintype "passive"))
    )
    (net (code "57") (name "Net-(U1-e)") (class "Default")
      (node (ref "R11") (pin "1") (pinfunction "1_1") (pintype "passive"))
      (node (ref "U1") (pin "9") (pinfunction "e_9") (pintype "passive"))
    )
    (net (code "58") (name "Net-(U1-f)") (class "Default")
      (node (ref "R5") (pin "1") (pinfunction "1_1") (pintype "passive"))
      (node (ref "U1") (pin "15") (pinfunction "f_15") (pintype "passive"))
    )
    (net (code "59") (name "Net-(U1-g)") (class "Default")
      (node (ref "R6") (pin "1") (pinfunction "1_1") (pintype "passive"))
      (node (ref "U1") (pin "14") (pinfunction "g_14") (pintype "passive"))
    )
    (net (code "60") (name "Net-(U2-RCO)") (class "Default")
      (node (ref "U2") (pin "15") (pinfunction "RCO_15") (pintype "passive"))
      (node (ref "U5") (pin "1") (pinfunction "1A_1") (pintype "passive"))
      (node (ref "U5") (pin "2") (pinfunction "1B_2") (pintype "passive"))
    )
    (net (code "61") (name "Net-(U3-A)") (class "Default")
      (node (ref "U3") (pin "7") (pinfunction "A_7") (pintype "passive"))
      (node (ref "U4") (pin "14") (pinfunction "QA_14") (pintype "passive"))
      (node (ref "U5") (pin "4") (pinfunction "2A_4") (pintype "passive"))
    )
    (net (code "62") (name "Net-(U3-B)") (class "Default")
      (node (ref "U3") (pin "1") (pinfunction "B_1") (pintype "passive"))
      (node (ref "U4") (pin "13") (pinfunction "QB_13") (pintype "passive"))
    )
    (net (code "63") (name "Net-(U3-C)") (class "Default")
      (node (ref "U3") (pin "2") (pinfunction "C_2") (pintype "passive"))
      (node (ref "U4") (pin "12") (pinfunction "QC_12") (pintype "passive"))
      (node (ref "U5") (pin "5") (pinfunction "2B_5") (pintype "passive"))
    )
    (net (code "64") (name "Net-(U3-D)") (class "Default")
      (node (ref "U3") (pin "6") (pinfunction "D_6") (pintype "passive"))
      (node (ref "U4") (pin "11") (pinfunction "QD_11") (pintype "passive"))
    )
    (net (code "65") (name "Net-(U3-a)") (class "Default")
      (node (ref "R14") (pin "1") (pinfunction "1_1") (pintype "passive"))
      (node (ref "U3") (pin "13") (pinfunction "a_13") (pintype "passive"))
    )
    (net (code "66") (name "Net-(U3-b)") (class "Default")
      (node (ref "R15") (pin "1") (pinfunction "1_1") (pintype "passive"))
      (node (ref "U3") (pin "12") (pinfunction "b_12") (pintype "passive"))
    )
    (net (code "67") (name "Net-(U3-c)") (class "Default")
      (node (ref "R16") (pin "1") (pinfunction "1_1") (pintype "passive"))
      (node (ref "U3") (pin "11") (pinfunction "c_11") (pintype "passive"))
    )
    (net (code "68") (name "Net-(U3-d)") (class "Default")
      (node (ref "R17") (pin "1") (pinfunction "1_1") (pintype "passive"))
      (node (ref "U3") (pin "10") (pinfunction "d_10") (pintype "passive"))
    )
    (net (code "69") (name "Net-(U3-e)") (class "Default")
      (node (ref "R18") (pin "1") (pinfunction "1_1") (pintype "passive"))
      (node (ref "U3") (pin "9") (pinfunction "e_9") (pintype "passive"))
    )
    (net (code "70") (name "Net-(U3-f)") (class "Default")
      (node (ref "R12") (pin "1") (pinfunction "1_1") (pintype "passive"))
      (node (ref "U3") (pin "15") (pinfunction "f_15") (pintype "passive"))
    )
    (net (code "71") (name "Net-(U3-g)") (class "Default")
      (node (ref "R13") (pin "1") (pinfunction "1_1") (pintype "passive"))
      (node (ref "U3") (pin "14") (pinfunction "g_14") (pintype "passive"))
    )
    (net (code "72") (name "Net-(U4-CLK)") (class "Default")
      (node (ref "U4") (pin "2") (pinfunction "CLK_2") (pintype "passive"))
      (node (ref "U5") (pin "3") (pinfunction "1Y_3") (pintype "passive"))
    )
    (net (code "73") (name "Net-(U5-3A)") (class "Default")
      (node (ref "U5") (pin "10") (pinfunction "3A_10") (pintype "passive"))
      (node (ref "U8") (pin "2") (pinfunction "C_2") (pintype "passive"))
      (node (ref "U9") (pin "12") (pinfunction "QC_12") (pintype "passive"))
    )
    (net (code "74") (name "Net-(U5-3B)") (class "Default")
      (node (ref "U5") (pin "9") (pinfunction "3B_9") (pintype "passive"))
      (node (ref "U8") (pin "7") (pinfunction "A_7") (pintype "passive"))
      (node (ref "U9") (pin "14") (pinfunction "QA_14") (pintype "passive"))
    )
    (net (code "75") (name "Net-(U5-4A)") (class "Default")
      (node (ref "U5") (pin "12") (pinfunction "4B_12") (pintype "passive"))
      (node (ref "U5") (pin "13") (pinfunction "4A_13") (pintype "passive"))
      (node (ref "U7") (pin "15") (pinfunction "RCO_15") (pintype "passive"))
    )
    (net (code "76") (name "Net-(U5-4Y)") (class "Default")
      (node (ref "U5") (pin "11") (pinfunction "4Y_11") (pintype "passive"))
      (node (ref "U9") (pin "2") (pinfunction "CLK_2") (pintype "passive"))
    )
    (net (code "77") (name "Net-(U6-A)") (class "Default")
      (node (ref "U6") (pin "7") (pinfunction "A_7") (pintype "passive"))
      (node (ref "U7") (pin "14") (pinfunction "QA_14") (pintype "passive"))
    )
    (net (code "78") (name "Net-(U6-B)") (class "Default")
      (node (ref "U6") (pin "1") (pinfunction "B_1") (pintype "passive"))
      (node (ref "U7") (pin "13") (pinfunction "QB_13") (pintype "passive"))
    )
    (net (code "79") (name "Net-(U6-C)") (class "Default")
      (node (ref "U6") (pin "2") (pinfunction "C_2") (pintype "passive"))
      (node (ref "U7") (pin "12") (pinfunction "QC_12") (pintype "passive"))
    )
    (net (code "80") (name "Net-(U6-D)") (class "Default")
      (node (ref "U6") (pin "6") (pinfunction "D_6") (pintype "passive"))
      (node (ref "U7") (pin "11") (pinfunction "QD_11") (pintype "passive"))
    )
    (net (code "81") (name "Net-(U6-a)") (class "Default")
      (node (ref "R21") (pin "1") (pinfunction "1_1") (pintype "passive"))
      (node (ref "U6") (pin "13") (pinfunction "a_13") (pintype "passive"))
    )
    (net (code "82") (name "Net-(U6-b)") (class "Default")
      (node (ref "R22") (pin "1") (pinfunction "1_1") (pintype "passive"))
      (node (ref "U6") (pin "12") (pinfunction "b_12") (pintype "passive"))
    )
    (net (code "83") (name "Net-(U6-c)") (class "Default")
      (node (ref "R23") (pin "1") (pinfunction "1_1") (pintype "passive"))
      (node (ref "U6") (pin "11") (pinfunction "c_11") (pintype "passive"))
    )
    (net (code "84") (name "Net-(U6-d)") (class "Default")
      (node (ref "R24") (pin "1") (pinfunction "1_1") (pintype "passive"))
      (node (ref "U6") (pin "10") (pinfunction "d_10") (pintype "passive"))
    )
    (net (code "85") (name "Net-(U6-e)") (class "Default")
      (node (ref "R25") (pin "1") (pinfunction "1_1") (pintype "passive"))
      (node (ref "U6") (pin "9") (pinfunction "e_9") (pintype "passive"))
    )
    (net (code "86") (name "Net-(U6-f)") (class "Default")
      (node (ref "R19") (pin "1") (pinfunction "1_1") (pintype "passive"))
      (node (ref "U6") (pin "15") (pinfunction "f_15") (pintype "passive"))
    )
    (net (code "87") (name "Net-(U6-g)") (class "Default")
      (node (ref "R20") (pin "1") (pinfunction "1_1") (pintype "passive"))
      (node (ref "U6") (pin "14") (pinfunction "g_14") (pintype "passive"))
    )
    (net (code "88") (name "Net-(U8-B)") (class "Default")
      (node (ref "U8") (pin "1") (pinfunction "B_1") (pintype "passive"))
      (node (ref "U9") (pin "13") (pinfunction "QB_13") (pintype "passive"))
    )
    (net (code "89") (name "Net-(U8-D)") (class "Default")
      (node (ref "U8") (pin "6") (pinfunction "D_6") (pintype "passive"))
      (node (ref "U9") (pin "11") (pinfunction "QD_11") (pintype "passive"))
    )
    (net (code "90") (name "Net-(U8-a)") (class "Default")
      (node (ref "R28") (pin "1") (pinfunction "1_1") (pintype "passive"))
      (node (ref "U8") (pin "13") (pinfunction "a_13") (pintype "passive"))
    )
    (net (code "91") (name "Net-(U8-b)") (class "Default")
      (node (ref "R29") (pin "1") (pinfunction "1_1") (pintype "passive"))
      (node (ref "U8") (pin "12") (pinfunction "b_12") (pintype "passive"))
    )
    (net (code "92") (name "Net-(U8-c)") (class "Default")
      (node (ref "R30") (pin "1") (pinfunction "1_1") (pintype "passive"))
      (node (ref "U8") (pin "11") (pinfunction "c_11") (pintype "passive"))
    )
    (net (code "93") (name "Net-(U8-d)") (class "Default")
      (node (ref "R31") (pin "1") (pinfunction "1_1") (pintype "passive"))
      (node (ref "U8") (pin "10") (pinfunction "d_10") (pintype "passive"))
    )
    (net (code "94") (name "Net-(U8-e)") (class "Default")
      (node (ref "R32") (pin "1") (pinfunction "1_1") (pintype "passive"))
      (node (ref "U8") (pin "9") (pinfunction "e_9") (pintype "passive"))
    )
    (net (code "95") (name "Net-(U8-f)") (class "Default")
      (node (ref "R26") (pin "1") (pinfunction "1_1") (pintype "passive"))
      (node (ref "U8") (pin "15") (pinfunction "f_15") (pintype "passive"))
    )
    (net (code "96") (name "Net-(U8-g)") (class "Default")
      (node (ref "R27") (pin "1") (pinfunction "1_1") (pintype "passive"))
      (node (ref "U8") (pin "14") (pinfunction "g_14") (pintype "passive"))
    )
    (net (code "97") (name "Net-(U10-4B)") (class "Default")
      (node (ref "U10") (pin "12") (pinfunction "4B_12") (pintype "passive"))
      (node (ref "U13") (pin "1") (pinfunction "B_1") (pintype "passive"))
      (node (ref "U14") (pin "13") (pinfunction "QB_13") (pintype "passive"))
    )
    (net (code "98") (name "Net-(U10-4Y)") (class "Default")
      (node (ref "U10") (pin "11") (pinfunction "4Y_11") (pintype "passive"))
      (node (ref "U12") (pin "9") (pinfunction "LOAD#_9") (pintype "passive"))
      (node (ref "U14") (pin "9") (pinfunction "LOAD#_9") (pintype "passive"))
    )
    (net (code "99") (name "Net-(U11-C)") (class "Default")
      (node (ref "U11") (pin "2") (pinfunction "C_2") (pintype "passive"))
      (node (ref "U12") (pin "12") (pinfunction "QC_12") (pintype "passive"))
    )
    (net (code "100") (name "Net-(U11-D)") (class "Default")
      (node (ref "U11") (pin "6") (pinfunction "D_6") (pintype "passive"))
      (node (ref "U12") (pin "11") (pinfunction "QD_11") (pintype "passive"))
    )
    (net (code "101") (name "Net-(U11-a)") (class "Default")
      (node (ref "R35") (pin "1") (pinfunction "1_1") (pintype "passive"))
      (node (ref "U11") (pin "13") (pinfunction "a_13") (pintype "passive"))
    )
    (net (code "102") (name "Net-(U11-b)") (class "Default")
      (node (ref "R36") (pin "1") (pinfunction "1_1") (pintype "passive"))
      (node (ref "U11") (pin "12") (pinfunction "b_12") (pintype "passive"))
    )
    (net (code "103") (name "Net-(U11-c)") (class "Default")
      (node (ref "R37") (pin "1") (pinfunction "1_1") (pintype "passive"))
      (node (ref "U11") (pin "11") (pinfunction "c_11") (pintype "passive"))
    )
    (net (code "104") (name "Net-(U11-d)") (class "Default")
      (node (ref "R38") (pin "1") (pinfunction "1_1") (pintype "passive"))
      (node (ref "U11") (pin "10") (pinfunction "d_10") (pintype "passive"))
    )
    (net (code "105") (name "Net-(U11-e)") (class "Default")
      (node (ref "R39") (pin "1") (pinfunction "1_1") (pintype "passive"))
      (node (ref "U11") (pin "9") (pinfunction "e_9") (pintype "passive"))
    )
    (net (code "106") (name "Net-(U11-f)") (class "Default")
      (node (ref "R33") (pin "1") (pinfunction "1_1") (pintype "passive"))
      (node (ref "U11") (pin "15") (pinfunction "f_15") (pintype "passive"))
    )
    (net (code "107") (name "Net-(U11-g)") (class "Default")
      (node (ref "R34") (pin "1") (pinfunction "1_1") (pintype "passive"))
      (node (ref "U11") (pin "14") (pinfunction "g_14") (pintype "passive"))
    )
    (net (code "108") (name "Net-(U12-RCO)") (class "Default")
      (node (ref "U12") (pin "15") (pinfunction "RCO_15") (pintype "passive"))
      (node (ref "U14") (pin "10") (pinfunction "ENT_10") (pintype "passive"))
      (node (ref "U14") (pin "7") (pinfunction "ENP_7") (pintype "passive"))
    )
    (net (code "109") (name "Net-(U13-A)") (class "Default")
      (node (ref "U13") (pin "7") (pinfunction "A_7") (pintype "passive"))
      (node (ref "U14") (pin "14") (pinfunction "QA_14") (pintype "passive"))
    )
    (net (code "110") (name "Net-(U13-C)") (class "Default")
      (node (ref "U13") (pin "2") (pinfunction "C_2") (pintype "passive"))
      (node (ref "U14") (pin "12") (pinfunction "QC_12") (pintype "passive"))
    )
    (net (code "111") (name "Net-(U13-D)") (class "Default")
      (node (ref "U13") (pin "6") (pinfunction "D_6") (pintype "passive"))
      (node (ref "U14") (pin "11") (pinfunction "QD_11") (pintype "passive"))
    )
    (net (code "112") (name "Net-(U13-a)") (class "Default")
      (node (ref "R42") (pin "1") (pinfunction "1_1") (pintype "passive"))
      (node (ref "U13") (pin "13") (pinfunction "a_13") (pintype "passive"))
    )
    (net (code "113") (name "Net-(U13-b)") (class "Default")
      (node (ref "R43") (pin "1") (pinfunction "1_1") (pintype "passive"))
      (node (ref "U13") (pin "12") (pinfunction "b_12") (pintype "passive"))
    )
    (net (code "114") (name "Net-(U13-c)") (class "Default")
      (node (ref "R44") (pin "1") (pinfunction "1_1") (pintype "passive"))
      (node (ref "U13") (pin "11") (pinfunction "c_11") (pintype "passive"))
    )
    (net (code "115") (name "Net-(U13-d)") (class "Default")
      (node (ref "R45") (pin "1") (pinfunction "1_1") (pintype "passive"))
      (node (ref "U13") (pin "10") (pinfunction "d_10") (pintype "passive"))
    )
    (net (code "116") (name "Net-(U13-e)") (class "Default")
      (node (ref "R46") (pin "1") (pinfunction "1_1") (pintype "passive"))
      (node (ref "U13") (pin "9") (pinfunction "e_9") (pintype "passive"))
    )
    (net (code "117") (name "Net-(U13-f)") (class "Default")
      (node (ref "R40") (pin "1") (pinfunction "1_1") (pintype "passive"))
      (node (ref "U13") (pin "15") (pinfunction "f_15") (pintype "passive"))
    )
    (net (code "118") (name "Net-(U13-g)") (class "Default")
      (node (ref "R41") (pin "1") (pinfunction "1_1") (pintype "passive"))
      (node (ref "U13") (pin "14") (pinfunction "g_14") (pintype "passive"))
    )
    (net (code "119") (name "Net-(U15-1B)") (class "Default")
      (node (ref "M+1") (pin "1") (pinfunction "1_1") (pintype "passive"))
      (node (ref "R4") (pin "2") (pinfunction "2_2") (pintype "passive"))
      (node (ref "U15") (pin "2") (pinfunction "1B_2") (pintype "passive"))
    )
    (net (code "120") (name "Net-(U15-2B)") (class "Default")
      (node (ref "H+1") (pin "1") (pinfunction "1_1") (pintype "passive"))
      (node (ref "R47") (pin "2") (pinfunction "2_2") (pintype "passive"))
      (node (ref "U15") (pin "5") (pinfunction "2B_5") (pintype "passive"))
    )
    (net (code "121") (name "Net-(U16-CONT)") (class "Default")
      (node (ref "C1") (pin "1") (pinfunction "1_1") (pintype "passive"))
      (node (ref "U16") (pin "5") (pinfunction "CONT_5") (pintype "passive"))
    )
    (net (code "122") (name "Net-(U16-DISCH)") (class "Default")
      (node (ref "R1") (pin "1") (pinfunction "1_1") (pintype "passive"))
      (node (ref "R2") (pin "2") (pinfunction "2_2") (pintype "passive"))
      (node (ref "U16") (pin "7") (pinfunction "DISCH_7") (pintype "passive"))
    )
    (net (code "123") (name "Net-(U16-THRES)") (class "Default")
      (node (ref "C2") (pin "1") (pinfunction "1_1") (pintype "passive"))
      (node (ref "R2") (pin "1") (pinfunction "1_1") (pintype "passive"))
      (node (ref "U16") (pin "2") (pinfunction "TRIG_2") (pintype "passive"))
      (node (ref "U16") (pin "6") (pinfunction "THRES_6") (pintype "passive"))
    )
    (net (code "124") (name "VCC") (class "Default")
      (node (ref "C3") (pin "1") (pinfunction "1_1") (pintype "passive"))
      (node (ref "P1") (pin "A9") (pinfunction "VBUS_A9") (pintype "passive"))
      (node (ref "R1") (pin "2") (pinfunction "2_2") (pintype "passive"))
      (node (ref "R3") (pin "1") (pinfunction "1_1") (pintype "passive"))
      (node (ref "R4") (pin "1") (pinfunction "1_1") (pintype "passive"))
      (node (ref "R47") (pin "1") (pinfunction "1_1") (pintype "passive"))
      (node (ref "U1") (pin "16") (pinfunction "VCC_16") (pintype "passive"))
      (node (ref "U1") (pin "3") (pinfunction "LT#_3") (pintype "passive"))
      (node (ref "U1") (pin "4") (pinfunction "BI#_4") (pintype "passive"))
      (node (ref "U10") (pin "14") (pinfunction "VCC_14") (pintype "passive"))
      (node (ref "U11") (pin "16") (pinfunction "VCC_16") (pintype "passive"))
      (node (ref "U11") (pin "3") (pinfunction "LT#_3") (pintype "passive"))
      (node (ref "U11") (pin "4") (pinfunction "BI#_4") (pintype "passive"))
      (node (ref "U12") (pin "10") (pinfunction "ENT_10") (pintype "passive"))
      (node (ref "U12") (pin "16") (pinfunction "VCC_16") (pintype "passive"))
      (node (ref "U12") (pin "7") (pinfunction "ENP_7") (pintype "passive"))
      (node (ref "U13") (pin "16") (pinfunction "VCC_16") (pintype "passive"))
      (node (ref "U13") (pin "3") (pinfunction "LT#_3") (pintype "passive"))
      (node (ref "U13") (pin "4") (pinfunction "BI#_4") (pintype "passive"))
      (node (ref "U14") (pin "16") (pinfunction "VCC_16") (pintype "passive"))
      (node (ref "U15") (pin "14") (pinfunction "VCC_14") (pintype "passive"))
      (node (ref "U16") (pin "4") (pinfunction "RESET_4") (pintype "passive"))
      (node (ref "U16") (pin "8") (pinfunction "VCC_8") (pintype "passive"))
      (node (ref "U2") (pin "10") (pinfunction "ENT_10") (pintype "passive"))
      (node (ref "U2") (pin "16") (pinfunction "VCC_16") (pintype "passive"))
      (node (ref "U2") (pin "7") (pinfunction "ENP_7") (pintype "passive"))
      (node (ref "U2") (pin "9") (pinfunction "LOAD#_9") (pintype "passive"))
      (node (ref "U3") (pin "16") (pinfunction "VCC_16") (pintype "passive"))
      (node (ref "U3") (pin "3") (pinfunction "LT#_3") (pintype "passive"))
      (node (ref "U3") (pin "4") (pinfunction "BI#_4") (pintype "passive"))
      (node (ref "U4") (pin "10") (pinfunction "ENT_10") (pintype "passive"))
      (node (ref "U4") (pin "16") (pinfunction "VCC_16") (pintype "passive"))
      (node (ref "U4") (pin "7") (pinfunction "ENP_7") (pintype "passive"))
      (node (ref "U5") (pin "14") (pinfunction "VCC_14") (pintype "passive"))
      (node (ref "U6") (pin "16") (pinfunction "VCC_16") (pintype "passive"))
      (node (ref "U6") (pin "3") (pinfunction "LT#_3") (pintype "passive"))
      (node (ref "U6") (pin "4") (pinfunction "BI#_4") (pintype "passive"))
      (node (ref "U7") (pin "10") (pinfunction "ENT_10") (pintype "passive"))
      (node (ref "U7") (pin "16") (pinfunction "VCC_16") (pintype "passive"))
      (node (ref "U7") (pin "7") (pinfunction "ENP_7") (pintype "passive"))
      (node (ref "U7") (pin "9") (pinfunction "LOAD#_9") (pintype "passive"))
      (node (ref "U8") (pin "16") (pinfunction "VCC_16") (pintype "passive"))
      (node (ref "U8") (pin "3") (pinfunction "LT#_3") (pintype "passive"))
      (node (ref "U8") (pin "4") (pinfunction "BI#_4") (pintype "passive"))
      (node (ref "U9") (pin "10") (pinfunction "ENT_10") (pintype "passive"))
      (node (ref "U9") (pin "16") (pinfunction "VCC_16") (pintype "passive"))
      (node (ref "U9") (pin "7") (pinfunction "ENP_7") (pintype "passive"))
    )
    (net (code "125") (name "unconnected-(DS1-DP-Pad7)") (class "Default")
      (node (ref "DS1") (pin "7") (pinfunction "DP_7") (pintype "passive"))
    )
    (net (code "126") (name "unconnected-(DS2-DP-Pad7)") (class "Default")
      (node (ref "DS2") (pin "7") (pinfunction "DP_7") (pintype "passive"))
    )
    (net (code "127") (name "unconnected-(DS3-DP-Pad7)") (class "Default")
      (node (ref "DS3") (pin "7") (pinfunction "DP_7") (pintype "passive"))
    )
    (net (code "128") (name "unconnected-(DS4-DP-Pad7)") (class "Default")
      (node (ref "DS4") (pin "7") (pinfunction "DP_7") (pintype "passive"))
    )
    (net (code "129") (name "unconnected-(DS5-DP-Pad7)") (class "Default")
      (node (ref "DS5") (pin "7") (pinfunction "DP_7") (pintype "passive"))
    )
    (net (code "130") (name "unconnected-(DS6-DP-Pad7)") (class "Default")
      (node (ref "DS6") (pin "7") (pinfunction "DP_7") (pintype "passive"))
    )
    (net (code "131") (name "unconnected-(P1-ETH-Pad3)") (class "Default")
      (node (ref "P1") (pin "3") (pinfunction "ETH_3") (pintype "passive"))
    )
    (net (code "132") (name "unconnected-(P1-ETH-Pad4)") (class "Default")
      (node (ref "P1") (pin "4") (pinfunction "ETH_4") (pintype "passive"))
    )
    (net (code "133") (name "unconnected-(U4-RCO-Pad15)") (class "Default")
      (node (ref "U4") (pin "15") (pinfunction "RCO_15") (pintype "passive"))
    )
    (net (code "134") (name "unconnected-(U9-RCO-Pad15)") (class "Default")
      (node (ref "U9") (pin "15") (pinfunction "RCO_15") (pintype "passive"))
    )
    (net (code "135") (name "unconnected-(U10-1A-Pad1)") (class "Default")
      (node (ref "U10") (pin "1") (pinfunction "1A_1") (pintype "passive"))
    )
    (net (code "136") (name "unconnected-(U10-1B-Pad2)") (class "Default")
      (node (ref "U10") (pin "2") (pinfunction "1B_2") (pintype "passive"))
    )
    (net (code "137") (name "unconnected-(U10-1Y-Pad3)") (class "Default")
      (node (ref "U10") (pin "3") (pinfunction "1Y_3") (pintype "passive"))
    )
    (net (code "138") (name "unconnected-(U10-2A-Pad4)") (class "Default")
      (node (ref "U10") (pin "4") (pinfunction "2A_4") (pintype "passive"))
    )
    (net (code "139") (name "unconnected-(U10-2B-Pad5)") (class "Default")
      (node (ref "U10") (pin "5") (pinfunction "2B_5") (pintype "passive"))
    )
    (net (code "140") (name "unconnected-(U10-2Y-Pad6)") (class "Default")
      (node (ref "U10") (pin "6") (pinfunction "2Y_6") (pintype "passive"))
    )
    (net (code "141") (name "unconnected-(U10-3A-Pad10)") (class "Default")
      (node (ref "U10") (pin "10") (pinfunction "3A_10") (pintype "passive"))
    )
    (net (code "142") (name "unconnected-(U10-3B-Pad9)") (class "Default")
      (node (ref "U10") (pin "9") (pinfunction "3B_9") (pintype "passive"))
    )
    (net (code "143") (name "unconnected-(U10-3Y-Pad8)") (class "Default")
      (node (ref "U10") (pin "8") (pinfunction "3Y_8") (pintype "passive"))
    )
    (net (code "144") (name "unconnected-(U14-RCO-Pad15)") (class "Default")
      (node (ref "U14") (pin "15") (pinfunction "RCO_15") (pintype "passive"))
    )
    (net (code "145") (name "unconnected-(U15-3A-Pad9)") (class "Default")
      (node (ref "U15") (pin "9") (pinfunction "3A_9") (pintype "passive"))
    )
    (net (code "146") (name "unconnected-(U15-3B-Pad10)") (class "Default")
      (node (ref "U15") (pin "10") (pinfunction "3B_10") (pintype "passive"))
    )
    (net (code "147") (name "unconnected-(U15-3Y-Pad8)") (class "Default")
      (node (ref "U15") (pin "8") (pinfunction "3Y_8") (pintype "passive"))
    )
  )
)
